# GWLSensorv2.net
KiCad netlist of a schematic drawn in EAGLE
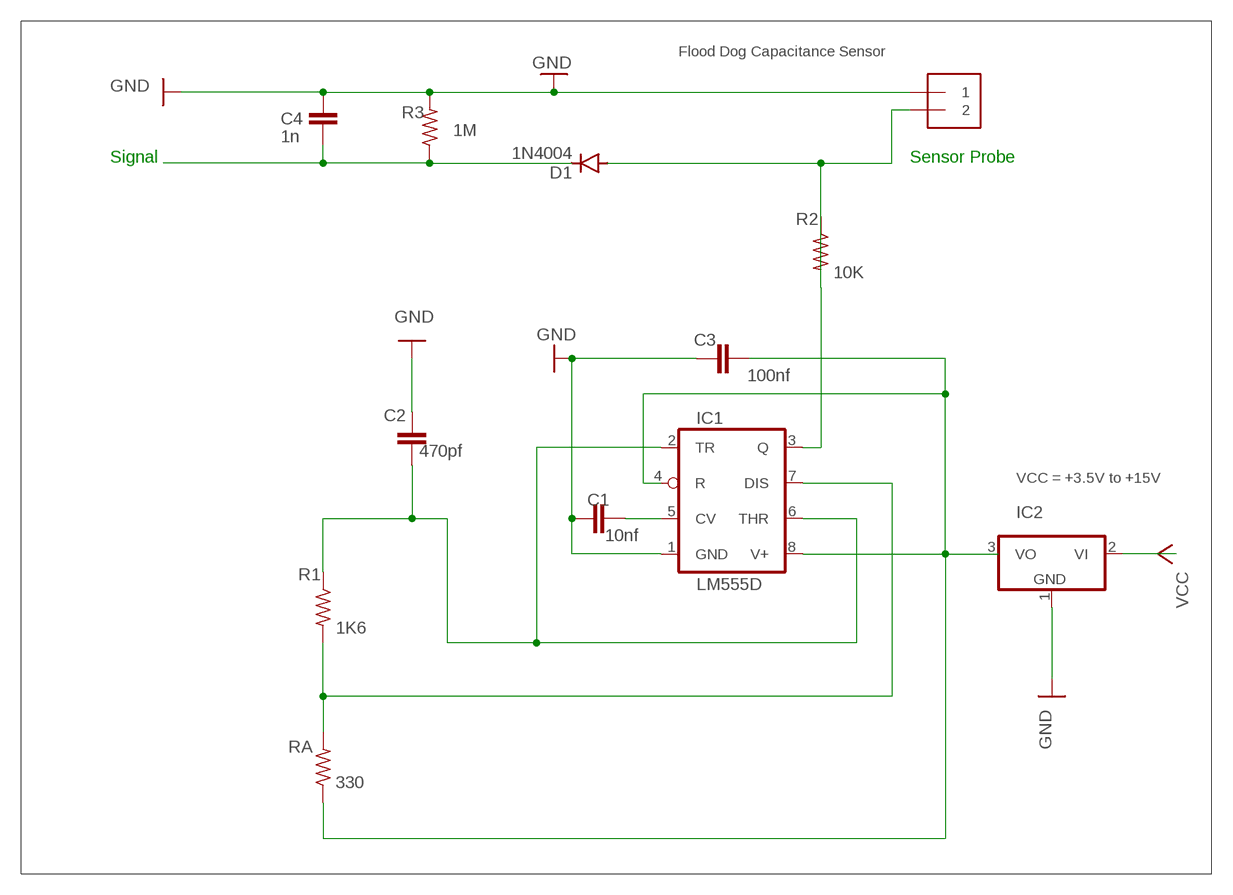
[diagram p0: schematic, sheet 1]

(export (version "E")
  (design (tool "Eeschema 10.0.6"))
  (components
    (comp (ref "C1")
      (value "10nf")
      (footprint "eagle-import:C0805")
      (libsource (lib "eagle-import") (part "C-EUC0805"))
    )
    (comp (ref "C2")
      (value "470pf")
      (footprint "eagle-import:C0805")
      (libsource (lib "eagle-import") (part "C-EUC0805"))
    )
    (comp (ref "C3")
      (value "100nf")
      (footprint "eagle-import:C0805")
      (libsource (lib "eagle-import") (part "C-EUC0805"))
    )
    (comp (ref "C4")
      (value "1n")
      (footprint "eagle-import:C0805")
      (libsource (lib "eagle-import") (part "C-EUC0805"))
    )
    (comp (ref "D1")
      (value "1N4004")
      (footprint "eagle-import:DO41-10")
      (libsource (lib "eagle-import") (part "1N4004"))
    )
    (comp (ref "IC1")
      (value "LM555D")
      (footprint "eagle-import:SO08")
      (libsource (lib "eagle-import") (part "555DLM"))
    )
    (comp (ref "IC2")
      (value "79L15Z")
      (footprint "eagle-import:TO92")
      (libsource (lib "eagle-import") (part "79ZL15"))
    )
    (comp (ref "J1")
      (value "1X2-3.5MM")
      (footprint "eagle-import:1X2-3.5MM")
      (libsource (lib "eagle-import") (part "1X2-3.5MM"))
    )
    (comp (ref "R1")
      (value "1K6")
      (footprint "eagle-import:R0805")
      (libsource (lib "eagle-import") (part "R-US_R0805"))
    )
    (comp (ref "R2")
      (value "10K")
      (footprint "eagle-import:R0805")
      (libsource (lib "eagle-import") (part "R-US_R0805"))
    )
    (comp (ref "R3")
      (value "1M")
      (footprint "eagle-import:R0805")
      (libsource (lib "eagle-import") (part "R-US_R0805"))
    )
    (comp (ref "RA")
      (value "330")
      (footprint "eagle-import:R0805")
      (libsource (lib "eagle-import") (part "R-US_R0805"))
    )
  )
  (nets
    (net (code "1") (name "GND") (class "Default")
      (node (ref "C1") (pin "1") (pinfunction "1_1") (pintype "passive"))
      (node (ref "C2") (pin "1") (pinfunction "1_1") (pintype "passive"))
      (node (ref "C3") (pin "1") (pinfunction "1_1") (pintype "passive"))
      (node (ref "C4") (pin "2") (pinfunction "2_2") (pintype "passive"))
      (node (ref "IC1") (pin "1") (pinfunction "GND_1") (pintype "power_in"))
      (node (ref "IC2") (pin "1") (pinfunction "GND_1") (pintype "passive"))
      (node (ref "J1") (pin "1") (pinfunction "1_1") (pintype "passive"))
      (node (ref "R3") (pin "2") (pinfunction "2_2") (pintype "passive"))
    )
    (net (code "2") (name "Net-(C4-Pad1)") (class "Default")
      (node (ref "C4") (pin "1") (pinfunction "1_1") (pintype "passive"))
      (node (ref "D1") (pin "C") (pinfunction "C_C") (pintype "passive"))
      (node (ref "R3") (pin "1") (pinfunction "1_1") (pintype "passive"))
    )
    (net (code "3") (name "Net-(IC1-CV)") (class "Default")
      (node (ref "C1") (pin "2") (pinfunction "2_2") (pintype "passive"))
      (node (ref "IC1") (pin "5") (pinfunction "CV_5") (pintype "input"))
    )
    (net (code "4") (name "Net-(IC1-DIS)") (class "Default")
      (node (ref "IC1") (pin "7") (pinfunction "DIS_7") (pintype "input"))
      (node (ref "R1") (pin "2") (pinfunction "2_2") (pintype "passive"))
      (node (ref "RA") (pin "2") (pinfunction "2_2") (pintype "passive"))
    )
    (net (code "5") (name "Net-(IC1-Q)") (class "Default")
      (node (ref "D1") (pin "A") (pinfunction "A_A") (pintype "passive"))
      (node (ref "IC1") (pin "3") (pinfunction "Q_3") (pintype "output"))
      (node (ref "J1") (pin "2") (pinfunction "2_2") (pintype "passive"))
      (node (ref "R2") (pin "1") (pinfunction "1_1") (pintype "passive"))
      (node (ref "R2") (pin "2") (pinfunction "2_2") (pintype "passive"))
    )
    (net (code "6") (name "Net-(IC1-R)") (class "Default")
      (node (ref "C3") (pin "2") (pinfunction "2_2") (pintype "passive"))
      (node (ref "IC1") (pin "4") (pinfunction "R_4") (pintype "input"))
      (node (ref "IC1") (pin "8") (pinfunction "V+_8") (pintype "power_in"))
      (node (ref "IC2") (pin "3") (pinfunction "VO_3") (pintype "passive"))
      (node (ref "RA") (pin "1") (pinfunction "1_1") (pintype "passive"))
    )
    (net (code "7") (name "Net-(IC1-THR)") (class "Default")
      (node (ref "C2") (pin "2") (pinfunction "2_2") (pintype "passive"))
      (node (ref "IC1") (pin "2") (pinfunction "TR_2") (pintype "input"))
      (node (ref "IC1") (pin "6") (pinfunction "THR_6") (pintype "input"))
      (node (ref "R1") (pin "1") (pinfunction "1_1") (pintype "passive"))
    )
    (net (code "8") (name "VCC") (class "Default")
      (node (ref "IC2") (pin "2") (pinfunction "VI_2") (pintype "input"))
    )
  )
)
